# mechanics.net
KiCad netlist of a schematic drawn in Altium Designer
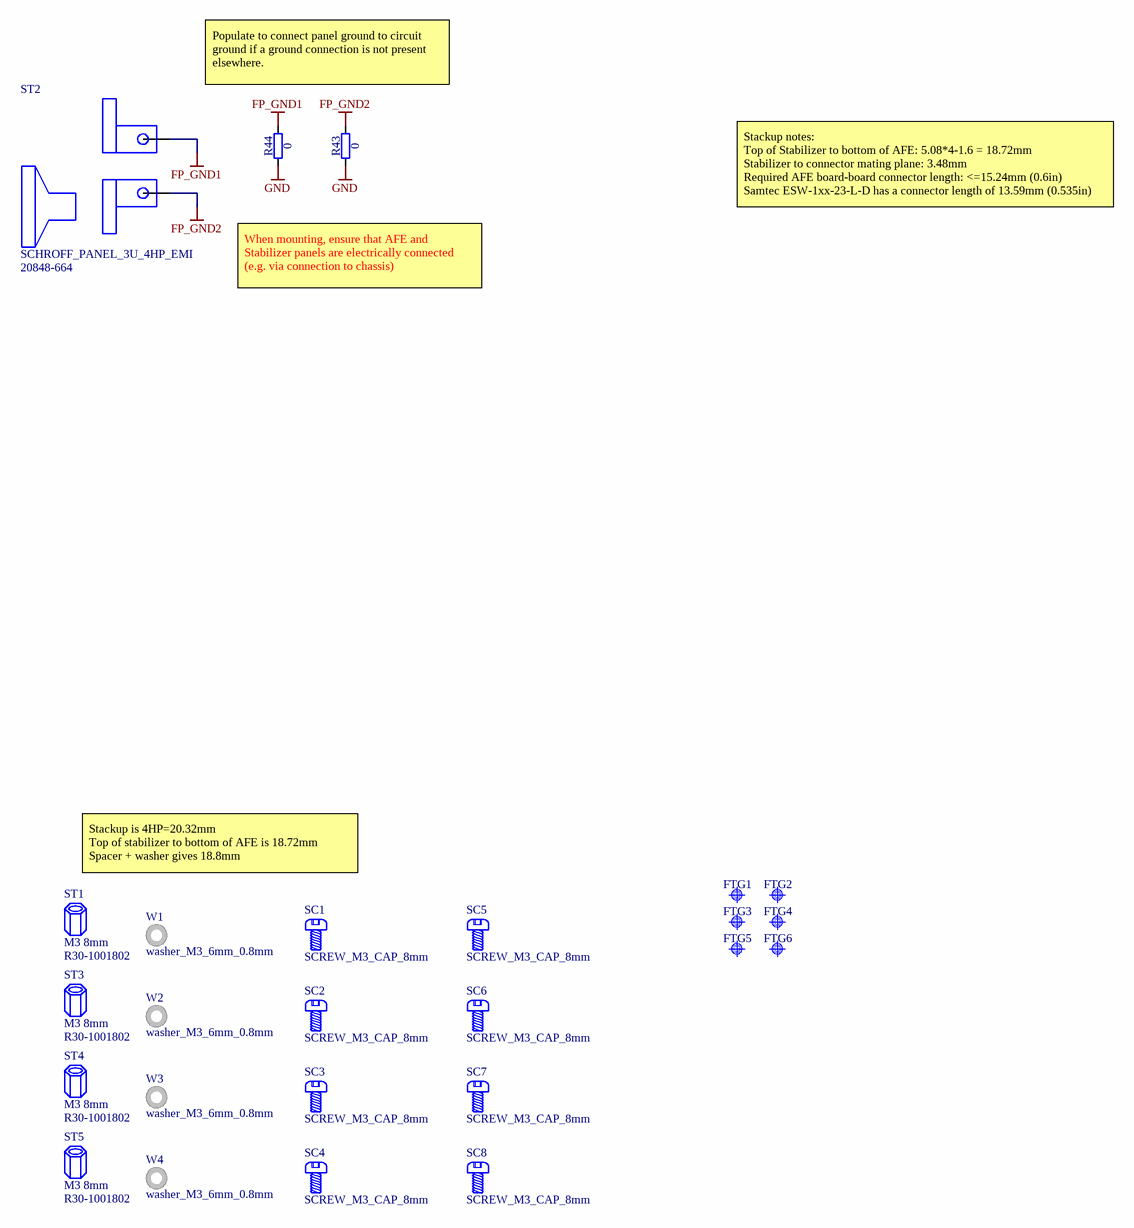
[diagram p0: mechanics.SchDoc]

(export (version "E")
  (design (tool "Eeschema 10.0.6"))
  (components
    (comp (ref "FTG1")
      (value "Use only in PCB")
      (footprint "FIDUCIAL_TOP_C100-200")
      (description "Fiducial Target")
      (fields (field (name "PART NUMBER") "FIDUCIAL_TARGET_C100-200") (field (name "AUTHOR") "CERN DEM JLC"))
      (libsource (lib "Eletro-mechanical") (part "Fiducial Target"))
    )
    (comp (ref "FTG2")
      (value "Use only in PCB")
      (footprint "FIDUCIAL_TOP_C100-200")
      (description "Fiducial Target")
      (fields (field (name "PART NUMBER") "FIDUCIAL_TARGET_C100-200") (field (name "AUTHOR") "CERN DEM JLC"))
      (libsource (lib "Eletro-mechanical") (part "Fiducial Target"))
    )
    (comp (ref "FTG3")
      (value "Use only in PCB")
      (footprint "FIDUCIAL_TOP_C100-200")
      (description "Fiducial Target")
      (fields (field (name "PART NUMBER") "FIDUCIAL_TARGET_C100-200") (field (name "AUTHOR") "CERN DEM JLC"))
      (libsource (lib "Eletro-mechanical") (part "Fiducial Target"))
    )
    (comp (ref "FTG4")
      (value "Use only in PCB")
      (footprint "FIDUCIAL_TOP_C100-200")
      (description "Fiducial Target")
      (fields (field (name "PART NUMBER") "FIDUCIAL_TARGET_C100-200") (field (name "AUTHOR") "CERN DEM JLC"))
      (libsource (lib "Eletro-mechanical") (part "Fiducial Target"))
    )
    (comp (ref "FTG5")
      (value "Use only in PCB")
      (footprint "FIDUCIAL_TOP_C100-200")
      (description "Fiducial Target")
      (fields (field (name "PART NUMBER") "FIDUCIAL_TARGET_C100-200") (field (name "AUTHOR") "CERN DEM JLC"))
      (libsource (lib "Eletro-mechanical") (part "Fiducial Target"))
    )
    (comp (ref "FTG6")
      (value "Use only in PCB")
      (footprint "FIDUCIAL_TOP_C100-200")
      (description "Fiducial Target")
      (fields (field (name "PART NUMBER") "FIDUCIAL_TARGET_C100-200") (field (name "AUTHOR") "CERN DEM JLC"))
      (libsource (lib "Eletro-mechanical") (part "Fiducial Target"))
    )
    (comp (ref "R43")
      (value "0")
      (footprint "RESC1608X55N")
      (description "Resistor")
      (fields
        (field (name "PART NUMBER") "R0603_0R_JUMPER")
        (field (name "MANUFACTURER") "GENERIC")
        (field (name "AUTHOR") "CERN DEM JLC")
      )
      (libsource (lib "Resistors") (part "Resistor"))
    )
    (comp (ref "R44")
      (value "0")
      (footprint "RESC1608X55N")
      (description "Resistor")
      (fields
        (field (name "PART NUMBER") "R0603_0R_JUMPER")
        (field (name "MANUFACTURER") "GENERIC")
        (field (name "AUTHOR") "CERN DEM JLC")
      )
      (libsource (lib "Resistors") (part "Resistor"))
    )
    (comp (ref "SC1")
      (value "SCREW_M3_CAP_8mm")
      (footprint "mechanical:SCREW_M3_CAP_8mm")
      (description "M3 x 8mm cap head screw")
      (fields
        (field (name "MANUFACTURER") "Accu Limited")
        (field (name "MANUFACTURER PART NUMBER") "SSCF-M3-8-12.9-Z")
      )
      (libsource (lib "mechanical") (part "SCREW_M3_CAP_8mm"))
    )
    (comp (ref "SC2")
      (value "SCREW_M3_CAP_8mm")
      (footprint "mechanical:SCREW_M3_CAP_8mm")
      (description "M3 x 8mm cap head screw")
      (fields
        (field (name "MANUFACTURER") "Accu Limited")
        (field (name "MANUFACTURER PART NUMBER") "SSCF-M3-8-12.9-Z")
      )
      (libsource (lib "mechanical") (part "SCREW_M3_CAP_8mm"))
    )
    (comp (ref "SC3")
      (value "SCREW_M3_CAP_8mm")
      (footprint "mechanical:SCREW_M3_CAP_8mm")
      (description "M3 x 8mm cap head screw")
      (fields
        (field (name "MANUFACTURER") "Accu Limited")
        (field (name "MANUFACTURER PART NUMBER") "SSCF-M3-8-12.9-Z")
      )
      (libsource (lib "mechanical") (part "SCREW_M3_CAP_8mm"))
    )
    (comp (ref "SC4")
      (value "SCREW_M3_CAP_8mm")
      (footprint "mechanical:SCREW_M3_CAP_8mm")
      (description "M3 x 8mm cap head screw")
      (fields
        (field (name "MANUFACTURER") "Accu Limited")
        (field (name "MANUFACTURER PART NUMBER") "SSCF-M3-8-12.9-Z")
      )
      (libsource (lib "mechanical") (part "SCREW_M3_CAP_8mm"))
    )
    (comp (ref "SC5")
      (value "SCREW_M3_CAP_8mm")
      (footprint "mechanical:SCREW_M3_CAP_8mm")
      (description "M3 x 8mm cap head screw")
      (fields
        (field (name "MANUFACTURER") "Accu Limited")
        (field (name "MANUFACTURER PART NUMBER") "SSCF-M3-8-12.9-Z")
      )
      (libsource (lib "mechanical") (part "SCREW_M3_CAP_8mm"))
    )
    (comp (ref "SC6")
      (value "SCREW_M3_CAP_8mm")
      (footprint "mechanical:SCREW_M3_CAP_8mm")
      (description "M3 x 8mm cap head screw")
      (fields
        (field (name "MANUFACTURER") "Accu Limited")
        (field (name "MANUFACTURER PART NUMBER") "SSCF-M3-8-12.9-Z")
      )
      (libsource (lib "mechanical") (part "SCREW_M3_CAP_8mm"))
    )
    (comp (ref "SC7")
      (value "SCREW_M3_CAP_8mm")
      (footprint "mechanical:SCREW_M3_CAP_8mm")
      (description "M3 x 8mm cap head screw")
      (fields
        (field (name "MANUFACTURER") "Accu Limited")
        (field (name "MANUFACTURER PART NUMBER") "SSCF-M3-8-12.9-Z")
      )
      (libsource (lib "mechanical") (part "SCREW_M3_CAP_8mm"))
    )
    (comp (ref "SC8")
      (value "SCREW_M3_CAP_8mm")
      (footprint "mechanical:SCREW_M3_CAP_8mm")
      (description "M3 x 8mm cap head screw")
      (fields
        (field (name "MANUFACTURER") "Accu Limited")
        (field (name "MANUFACTURER PART NUMBER") "SSCF-M3-8-12.9-Z")
      )
      (libsource (lib "mechanical") (part "SCREW_M3_CAP_8mm"))
    )
    (comp (ref "ST1")
      (value "M3 8mm")
      (footprint "mechanical:R30-1001802")
      (description "M3.0x18 standoff")
      (fields (field (name "MANUFACTURER") "Harwin") (field (name "MANUFACTURER PART NUMBER") "R30-1001802"))
      (libsource (lib "mechanical") (part "STANDOFF_HARWIN_R30_1001802"))
    )
    (comp (ref "ST2")
      (value "SCHROFF_PANEL_3U_4HP_EMI")
      (footprint "mechanical:SCHROFF_PANEL_3HP_4U")
      (description "Schroff 3HP 4U EUROCARD Panel with EMI gaskets kit")
      (fields (field (name "MANUFACTURER") "Schroff") (field (name "MANUFACTURER PART NUMBER") "20848-664"))
      (libsource (lib "mechanical") (part "SCHROFF_PANEL_3U_4HP_EMI"))
    )
    (comp (ref "ST3")
      (value "M3 8mm")
      (footprint "mechanical:R30-1001802")
      (description "M3.0x18 standoff")
      (fields (field (name "MANUFACTURER") "Harwin") (field (name "MANUFACTURER PART NUMBER") "R30-1001802"))
      (libsource (lib "mechanical") (part "STANDOFF_HARWIN_R30_1001802"))
    )
    (comp (ref "ST4")
      (value "M3 8mm")
      (footprint "mechanical:R30-1001802")
      (description "M3.0x18 standoff")
      (fields (field (name "MANUFACTURER") "Harwin") (field (name "MANUFACTURER PART NUMBER") "R30-1001802"))
      (libsource (lib "mechanical") (part "STANDOFF_HARWIN_R30_1001802"))
    )
    (comp (ref "ST5")
      (value "M3 8mm")
      (footprint "mechanical:R30-1001802")
      (description "M3.0x18 standoff")
      (fields (field (name "MANUFACTURER") "Harwin") (field (name "MANUFACTURER PART NUMBER") "R30-1001802"))
      (libsource (lib "mechanical") (part "STANDOFF_HARWIN_R30_1001802"))
    )
    (comp (ref "W1")
      (value "washer_M3_6mm_0.8mm")
      (footprint "mechanical:washer_M3_6mm_0.8mm")
      (description "M3 Washer:\r\nID: 3.2mm\r\nOD: 6mm\r\nThickness 0.8mm")
      (fields
        (field (name "MANUFACTURER") "Accu Limited")
        (field (name "MANUFACTURER PART NUMBER") "HAFZ-M3-A4")
      )
      (libsource (lib "mechanical") (part "washer_M3_6mm_0.8mm"))
    )
    (comp (ref "W2")
      (value "washer_M3_6mm_0.8mm")
      (footprint "mechanical:washer_M3_6mm_0.8mm")
      (description "M3 Washer:\r\nID: 3.2mm\r\nOD: 6mm\r\nThickness 0.8mm")
      (fields
        (field (name "MANUFACTURER") "Accu Limited")
        (field (name "MANUFACTURER PART NUMBER") "HAFZ-M3-A4")
      )
      (libsource (lib "mechanical") (part "washer_M3_6mm_0.8mm"))
    )
    (comp (ref "W3")
      (value "washer_M3_6mm_0.8mm")
      (footprint "mechanical:washer_M3_6mm_0.8mm")
      (description "M3 Washer:\r\nID: 3.2mm\r\nOD: 6mm\r\nThickness 0.8mm")
      (fields
        (field (name "MANUFACTURER") "Accu Limited")
        (field (name "MANUFACTURER PART NUMBER") "HAFZ-M3-A4")
      )
      (libsource (lib "mechanical") (part "washer_M3_6mm_0.8mm"))
    )
    (comp (ref "W4")
      (value "washer_M3_6mm_0.8mm")
      (footprint "mechanical:washer_M3_6mm_0.8mm")
      (description "M3 Washer:\r\nID: 3.2mm\r\nOD: 6mm\r\nThickness 0.8mm")
      (fields
        (field (name "MANUFACTURER") "Accu Limited")
        (field (name "MANUFACTURER PART NUMBER") "HAFZ-M3-A4")
      )
      (libsource (lib "mechanical") (part "washer_M3_6mm_0.8mm"))
    )
  )
  (nets
    (net (code "1") (name "FP_GND1") (class "Default")
      (node (ref "R44") (pin "2") (pinfunction "2_2") (pintype "passive"))
      (node (ref "ST2") (pin "1") (pinfunction "1_1") (pintype "passive"))
    )
    (net (code "2") (name "FP_GND2") (class "Default")
      (node (ref "R43") (pin "2") (pinfunction "2_2") (pintype "passive"))
      (node (ref "ST2") (pin "0") (pinfunction "0_0") (pintype "passive"))
    )
    (net (code "3") (name "GND") (class "Default")
      (node (ref "R43") (pin "1") (pinfunction "1_1") (pintype "passive"))
      (node (ref "R44") (pin "1") (pinfunction "1_1") (pintype "passive"))
    )
  )
)
